# Callisto_MSO_Teknic_v1p00.net
KiCad netlist of a schematic drawn in EAGLE
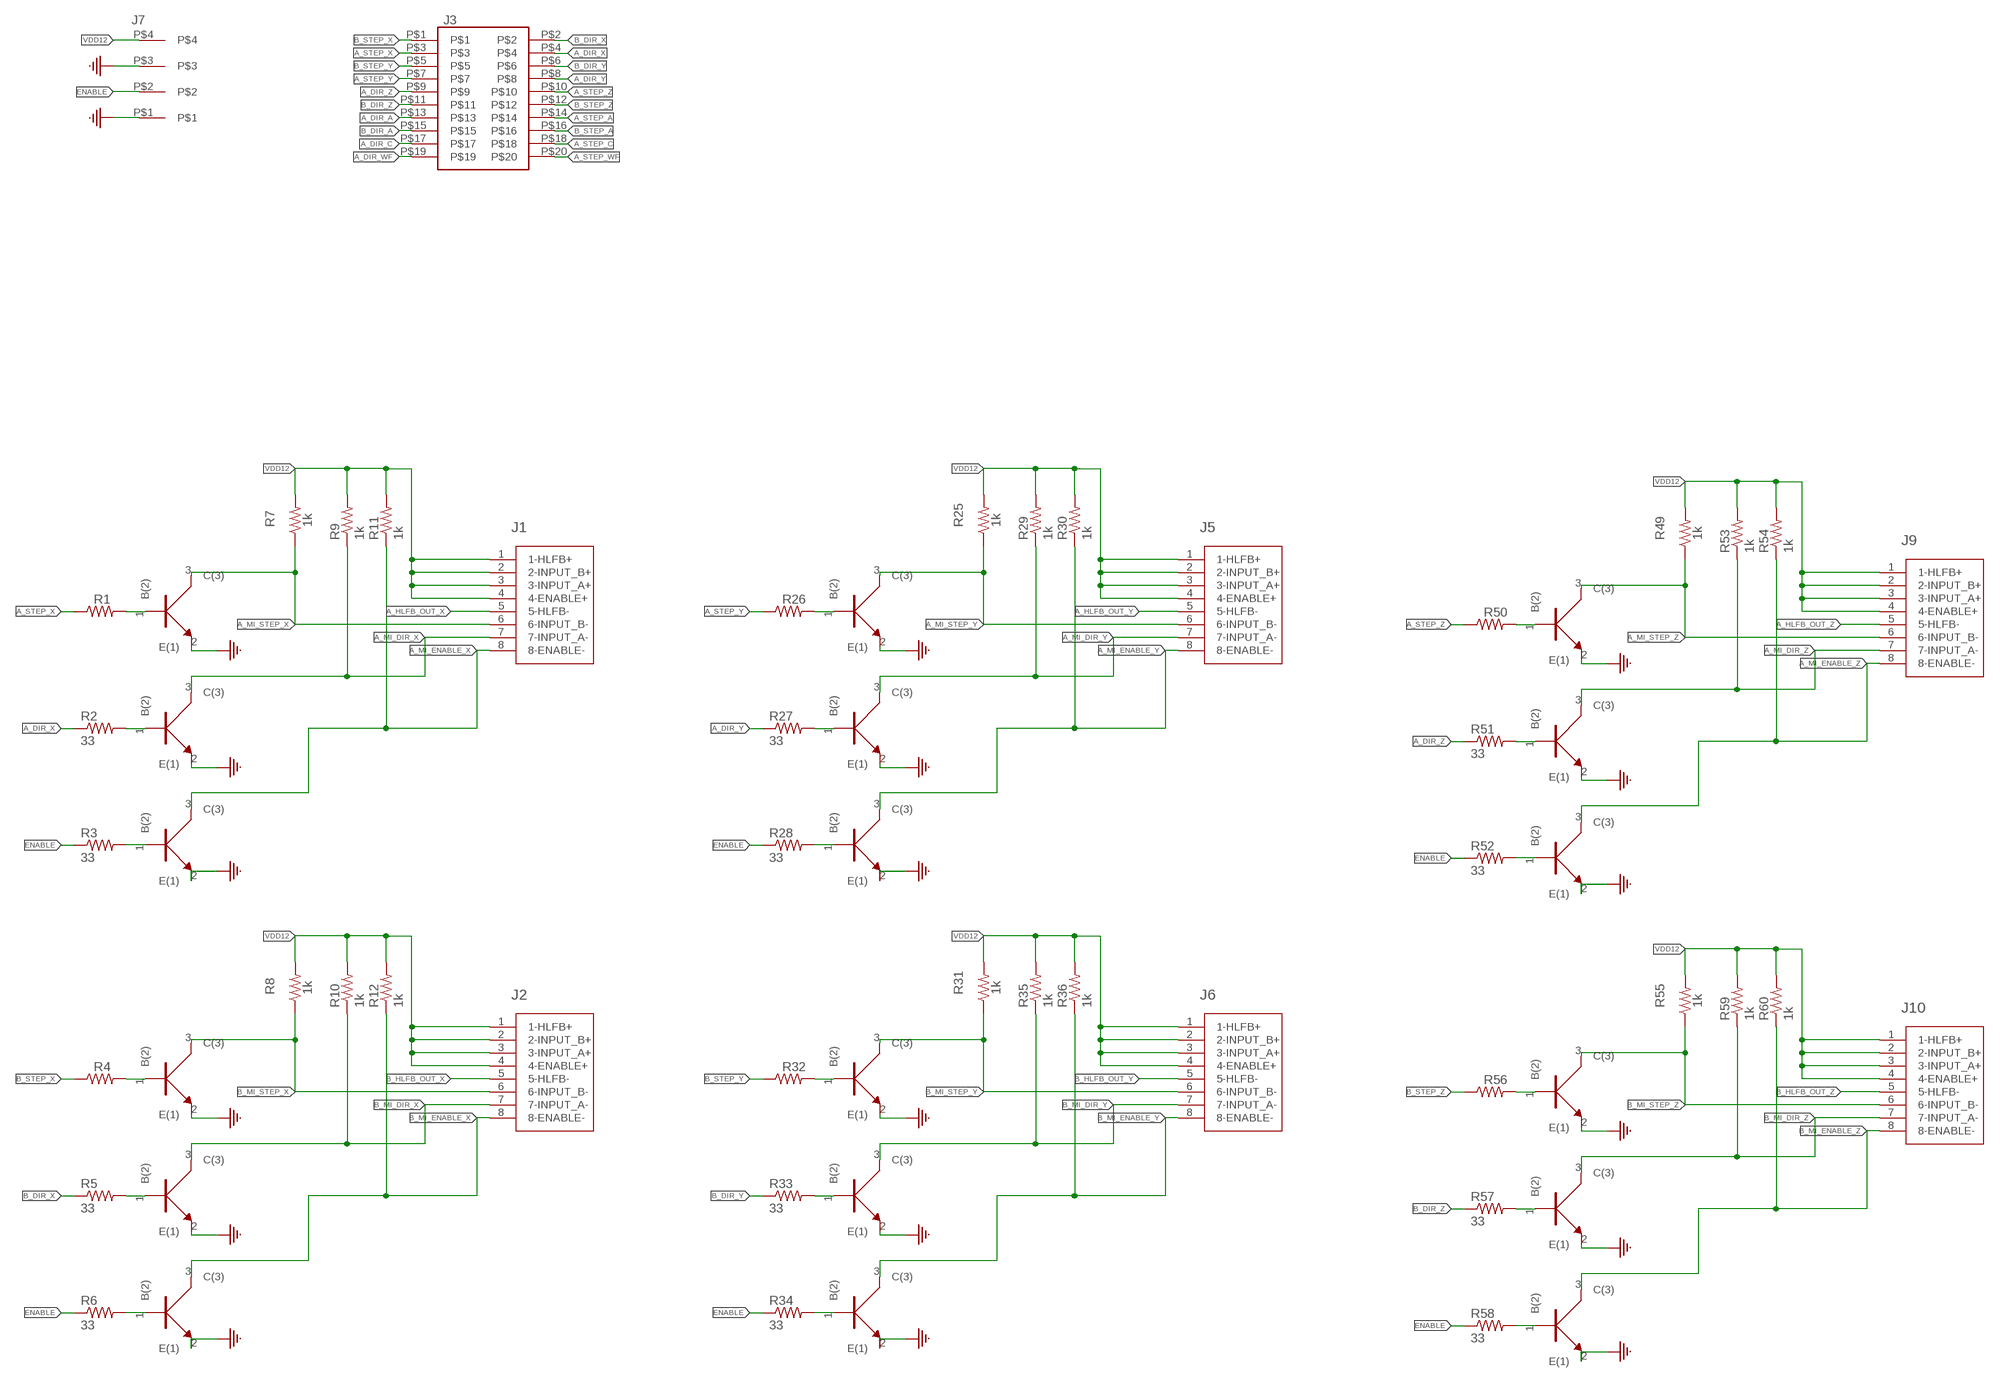
[diagram p0: schematic, sheet 1, part 1 of 2]
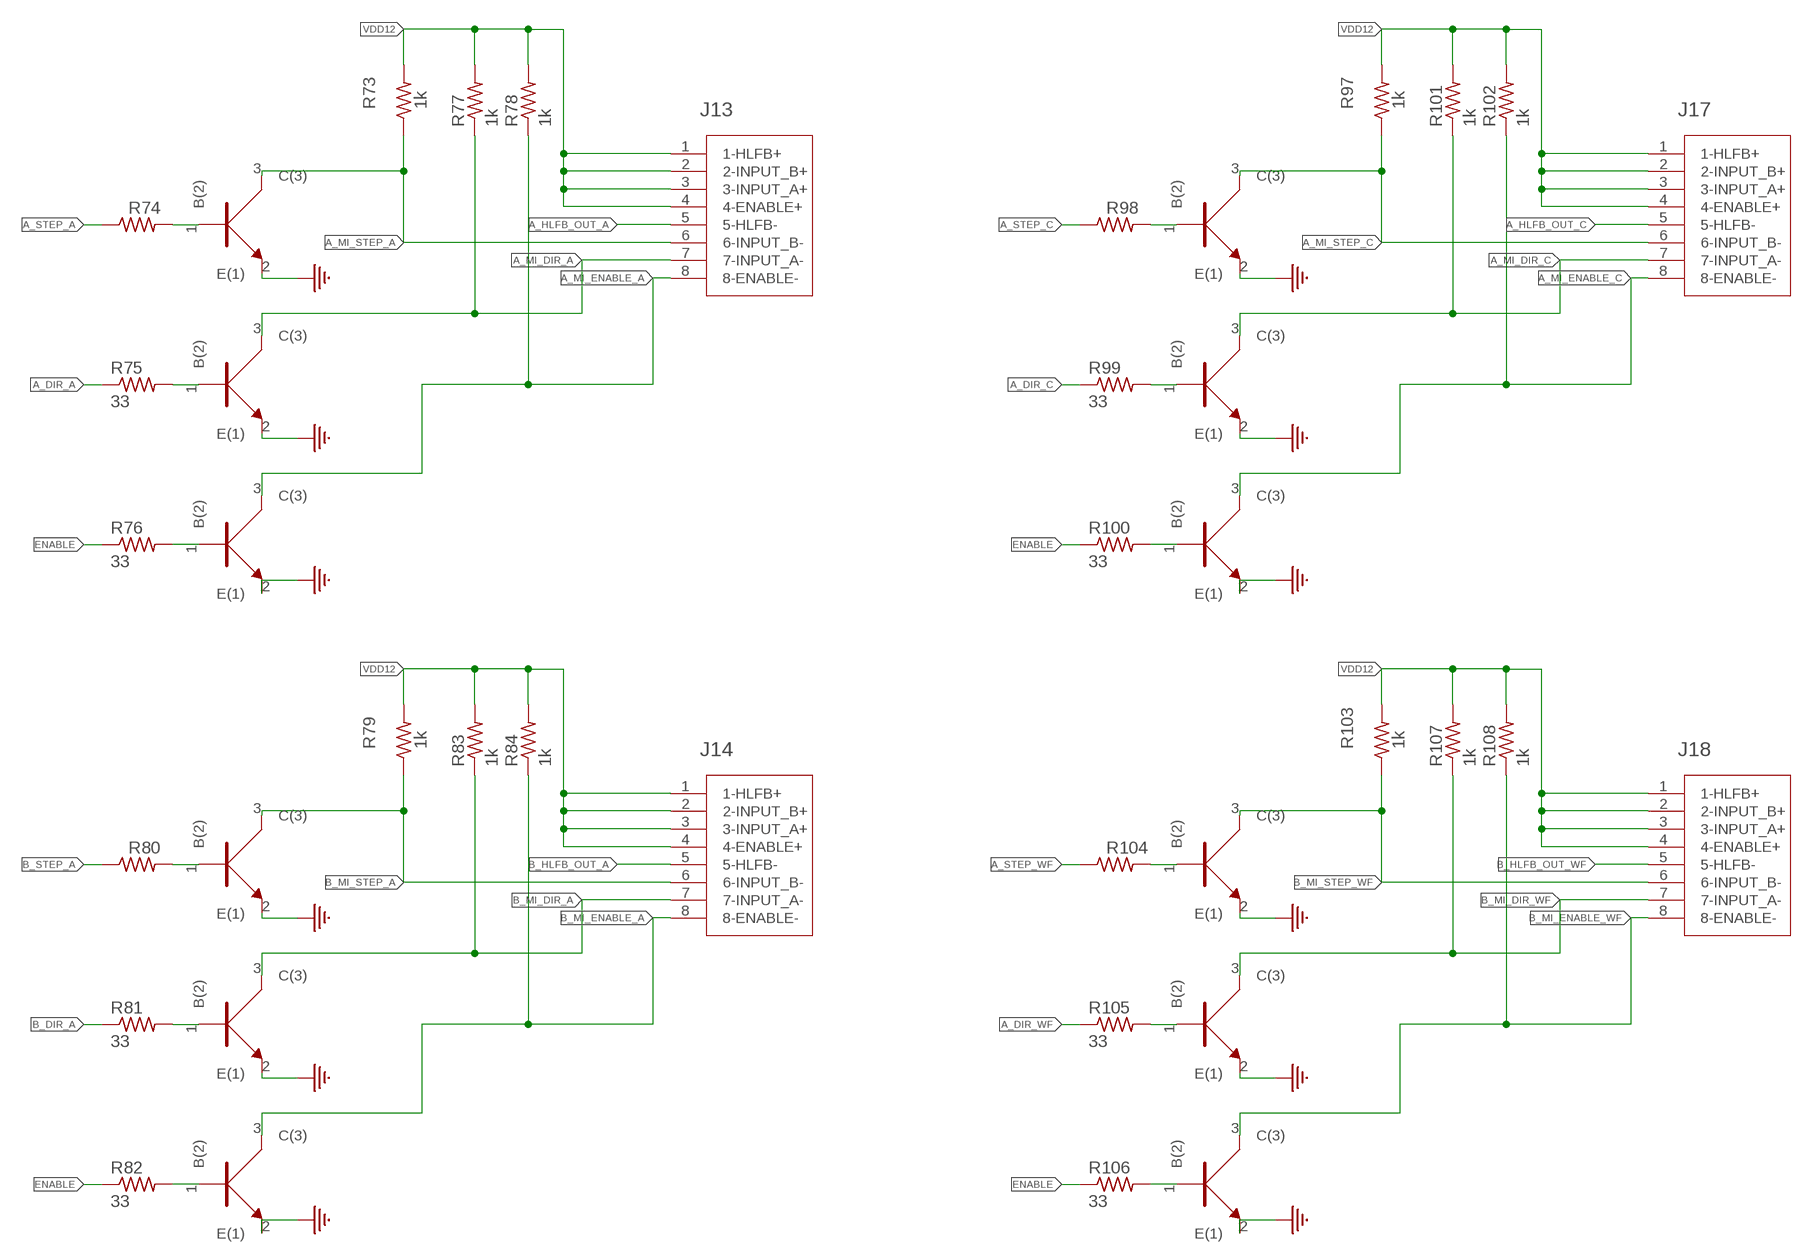
[diagram p1: schematic, sheet 1, part 2 of 2]

(export (version "E")
  (design (tool "Eeschema 10.0.6"))
  (components
    (comp (ref "J1")
      (value "TEKNIC_8PIN_MOTOR")
      (footprint "eagle-import:CON_39281083")
      (fields
        (field (name "MANUFACTURER_PART_NUMBER") "39281083")
        (field (name "COPYRIGHT") "Copyright (C) 2022 Ultra Librarian. All rights reserved.")
      )
      (libsource (lib "eagle-import") (part "TEKNIC_8PIN_MOTOR"))
    )
    (comp (ref "J2")
      (value "TEKNIC_8PIN_MOTOR")
      (footprint "eagle-import:CON_39281083")
      (fields
        (field (name "MANUFACTURER_PART_NUMBER") "39281083")
        (field (name "COPYRIGHT") "Copyright (C) 2022 Ultra Librarian. All rights reserved.")
      )
      (libsource (lib "eagle-import") (part "TEKNIC_8PIN_MOTOR"))
    )
    (comp (ref "J3")
      (value "2_X_10_HEADER_GENERIC2_X_10_.1_IN_RA")
      (footprint "eagle-import:2_X_10_.1_INCH")
      (fields (field (name "PARTNO") "PH2RA-20-UA"))
      (libsource (lib "eagle-import") (part "2_X_10_HEADER_GENERIC2_X_10_.1_IN_RA"))
    )
    (comp (ref "J5")
      (value "TEKNIC_8PIN_MOTOR")
      (footprint "eagle-import:CON_39281083")
      (fields
        (field (name "MANUFACTURER_PART_NUMBER") "39281083")
        (field (name "COPYRIGHT") "Copyright (C) 2022 Ultra Librarian. All rights reserved.")
      )
      (libsource (lib "eagle-import") (part "TEKNIC_8PIN_MOTOR"))
    )
    (comp (ref "J6")
      (value "TEKNIC_8PIN_MOTOR")
      (footprint "eagle-import:CON_39281083")
      (fields
        (field (name "MANUFACTURER_PART_NUMBER") "39281083")
        (field (name "COPYRIGHT") "Copyright (C) 2022 Ultra Librarian. All rights reserved.")
      )
      (libsource (lib "eagle-import") (part "TEKNIC_8PIN_MOTOR"))
    )
    (comp (ref "J7")
      (value "4-pos")
      (footprint "eagle-import:1X4_3.81MM_PITCH")
      (fields (field (name "PARTNO") "691322310004"))
      (libsource (lib "eagle-import") (part "3.81MM_1_X_4_RT_ANGLE_PLUG_HEADER"))
    )
    (comp (ref "J9")
      (value "TEKNIC_8PIN_MOTOR")
      (footprint "eagle-import:CON_39281083")
      (fields
        (field (name "MANUFACTURER_PART_NUMBER") "39281083")
        (field (name "COPYRIGHT") "Copyright (C) 2022 Ultra Librarian. All rights reserved.")
      )
      (libsource (lib "eagle-import") (part "TEKNIC_8PIN_MOTOR"))
    )
    (comp (ref "J10")
      (value "TEKNIC_8PIN_MOTOR")
      (footprint "eagle-import:CON_39281083")
      (fields
        (field (name "MANUFACTURER_PART_NUMBER") "39281083")
        (field (name "COPYRIGHT") "Copyright (C) 2022 Ultra Librarian. All rights reserved.")
      )
      (libsource (lib "eagle-import") (part "TEKNIC_8PIN_MOTOR"))
    )
    (comp (ref "J13")
      (value "TEKNIC_8PIN_MOTOR")
      (footprint "eagle-import:CON_39281083")
      (fields
        (field (name "MANUFACTURER_PART_NUMBER") "39281083")
        (field (name "COPYRIGHT") "Copyright (C) 2022 Ultra Librarian. All rights reserved.")
      )
      (libsource (lib "eagle-import") (part "TEKNIC_8PIN_MOTOR"))
    )
    (comp (ref "J14")
      (value "TEKNIC_8PIN_MOTOR")
      (footprint "eagle-import:CON_39281083")
      (fields
        (field (name "MANUFACTURER_PART_NUMBER") "39281083")
        (field (name "COPYRIGHT") "Copyright (C) 2022 Ultra Librarian. All rights reserved.")
      )
      (libsource (lib "eagle-import") (part "TEKNIC_8PIN_MOTOR"))
    )
    (comp (ref "J17")
      (value "TEKNIC_8PIN_MOTOR")
      (footprint "eagle-import:CON_39281083")
      (fields
        (field (name "MANUFACTURER_PART_NUMBER") "39281083")
        (field (name "COPYRIGHT") "Copyright (C) 2022 Ultra Librarian. All rights reserved.")
      )
      (libsource (lib "eagle-import") (part "TEKNIC_8PIN_MOTOR"))
    )
    (comp (ref "J18")
      (value "TEKNIC_8PIN_MOTOR")
      (footprint "eagle-import:CON_39281083")
      (fields
        (field (name "MANUFACTURER_PART_NUMBER") "39281083")
        (field (name "COPYRIGHT") "Copyright (C) 2022 Ultra Librarian. All rights reserved.")
      )
      (libsource (lib "eagle-import") (part "TEKNIC_8PIN_MOTOR"))
    )
    (comp (ref "R1")
      (value "33")
      (footprint "eagle-import:0805")
      (libsource (lib "eagle-import") (part "R_0805"))
    )
    (comp (ref "R2")
      (value "33")
      (footprint "eagle-import:0805")
      (libsource (lib "eagle-import") (part "R_0805"))
    )
    (comp (ref "R3")
      (value "33")
      (footprint "eagle-import:0805")
      (libsource (lib "eagle-import") (part "R_0805"))
    )
    (comp (ref "R4")
      (value "33")
      (footprint "eagle-import:0805")
      (libsource (lib "eagle-import") (part "R_0805"))
    )
    (comp (ref "R5")
      (value "33")
      (footprint "eagle-import:0805")
      (libsource (lib "eagle-import") (part "R_0805"))
    )
    (comp (ref "R6")
      (value "33")
      (footprint "eagle-import:0805")
      (libsource (lib "eagle-import") (part "R_0805"))
    )
    (comp (ref "R7")
      (value "1k")
      (footprint "eagle-import:0805")
      (libsource (lib "eagle-import") (part "R_0805"))
    )
    (comp (ref "R8")
      (value "1k")
      (footprint "eagle-import:0805")
      (libsource (lib "eagle-import") (part "R_0805"))
    )
    (comp (ref "R9")
      (value "1k")
      (footprint "eagle-import:0805")
      (libsource (lib "eagle-import") (part "R_0805"))
    )
    (comp (ref "R10")
      (value "1k")
      (footprint "eagle-import:0805")
      (libsource (lib "eagle-import") (part "R_0805"))
    )
    (comp (ref "R11")
      (value "1k")
      (footprint "eagle-import:0805")
      (libsource (lib "eagle-import") (part "R_0805"))
    )
    (comp (ref "R12")
      (value "1k")
      (footprint "eagle-import:0805")
      (libsource (lib "eagle-import") (part "R_0805"))
    )
    (comp (ref "R25")
      (value "1k")
      (footprint "eagle-import:0805")
      (libsource (lib "eagle-import") (part "R_0805"))
    )
    (comp (ref "R26")
      (value "33")
      (footprint "eagle-import:0805")
      (libsource (lib "eagle-import") (part "R_0805"))
    )
    (comp (ref "R27")
      (value "33")
      (footprint "eagle-import:0805")
      (libsource (lib "eagle-import") (part "R_0805"))
    )
    (comp (ref "R28")
      (value "33")
      (footprint "eagle-import:0805")
      (libsource (lib "eagle-import") (part "R_0805"))
    )
    (comp (ref "R29")
      (value "1k")
      (footprint "eagle-import:0805")
      (libsource (lib "eagle-import") (part "R_0805"))
    )
    (comp (ref "R30")
      (value "1k")
      (footprint "eagle-import:0805")
      (libsource (lib "eagle-import") (part "R_0805"))
    )
    (comp (ref "R31")
      (value "1k")
      (footprint "eagle-import:0805")
      (libsource (lib "eagle-import") (part "R_0805"))
    )
    (comp (ref "R32")
      (value "33")
      (footprint "eagle-import:0805")
      (libsource (lib "eagle-import") (part "R_0805"))
    )
    (comp (ref "R33")
      (value "33")
      (footprint "eagle-import:0805")
      (libsource (lib "eagle-import") (part "R_0805"))
    )
    (comp (ref "R34")
      (value "33")
      (footprint "eagle-import:0805")
      (libsource (lib "eagle-import") (part "R_0805"))
    )
    (comp (ref "R35")
      (value "1k")
      (footprint "eagle-import:0805")
      (libsource (lib "eagle-import") (part "R_0805"))
    )
    (comp (ref "R36")
      (value "1k")
      (footprint "eagle-import:0805")
      (libsource (lib "eagle-import") (part "R_0805"))
    )
    (comp (ref "R49")
      (value "1k")
      (footprint "eagle-import:0805")
      (libsource (lib "eagle-import") (part "R_0805"))
    )
    (comp (ref "R50")
      (value "33")
      (footprint "eagle-import:0805")
      (libsource (lib "eagle-import") (part "R_0805"))
    )
    (comp (ref "R51")
      (value "33")
      (footprint "eagle-import:0805")
      (libsource (lib "eagle-import") (part "R_0805"))
    )
    (comp (ref "R52")
      (value "33")
      (footprint "eagle-import:0805")
      (libsource (lib "eagle-import") (part "R_0805"))
    )
    (comp (ref "R53")
      (value "1k")
      (footprint "eagle-import:0805")
      (libsource (lib "eagle-import") (part "R_0805"))
    )
    (comp (ref "R54")
      (value "1k")
      (footprint "eagle-import:0805")
      (libsource (lib "eagle-import") (part "R_0805"))
    )
    (comp (ref "R55")
      (value "1k")
      (footprint "eagle-import:0805")
      (libsource (lib "eagle-import") (part "R_0805"))
    )
    (comp (ref "R56")
      (value "33")
      (footprint "eagle-import:0805")
      (libsource (lib "eagle-import") (part "R_0805"))
    )
    (comp (ref "R57")
      (value "33")
      (footprint "eagle-import:0805")
      (libsource (lib "eagle-import") (part "R_0805"))
    )
    (comp (ref "R58")
      (value "33")
      (footprint "eagle-import:0805")
      (libsource (lib "eagle-import") (part "R_0805"))
    )
    (comp (ref "R59")
      (value "1k")
      (footprint "eagle-import:0805")
      (libsource (lib "eagle-import") (part "R_0805"))
    )
    (comp (ref "R60")
      (value "1k")
      (footprint "eagle-import:0805")
      (libsource (lib "eagle-import") (part "R_0805"))
    )
    (comp (ref "R73")
      (value "1k")
      (footprint "eagle-import:0805")
      (libsource (lib "eagle-import") (part "R_0805"))
    )
    (comp (ref "R74")
      (value "33")
      (footprint "eagle-import:0805")
      (libsource (lib "eagle-import") (part "R_0805"))
    )
    (comp (ref "R75")
      (value "33")
      (footprint "eagle-import:0805")
      (libsource (lib "eagle-import") (part "R_0805"))
    )
    (comp (ref "R76")
      (value "33")
      (footprint "eagle-import:0805")
      (libsource (lib "eagle-import") (part "R_0805"))
    )
    (comp (ref "R77")
      (value "1k")
      (footprint "eagle-import:0805")
      (libsource (lib "eagle-import") (part "R_0805"))
    )
    (comp (ref "R78")
      (value "1k")
      (footprint "eagle-import:0805")
      (libsource (lib "eagle-import") (part "R_0805"))
    )
    (comp (ref "R79")
      (value "1k")
      (footprint "eagle-import:0805")
      (libsource (lib "eagle-import") (part "R_0805"))
    )
    (comp (ref "R80")
      (value "33")
      (footprint "eagle-import:0805")
      (libsource (lib "eagle-import") (part "R_0805"))
    )
    (comp (ref "R81")
      (value "33")
      (footprint "eagle-import:0805")
      (libsource (lib "eagle-import") (part "R_0805"))
    )
    (comp (ref "R82")
      (value "33")
      (footprint "eagle-import:0805")
      (libsource (lib "eagle-import") (part "R_0805"))
    )
    (comp (ref "R83")
      (value "1k")
      (footprint "eagle-import:0805")
      (libsource (lib "eagle-import") (part "R_0805"))
    )
    (comp (ref "R84")
      (value "1k")
      (footprint "eagle-import:0805")
      (libsource (lib "eagle-import") (part "R_0805"))
    )
    (comp (ref "R97")
      (value "1k")
      (footprint "eagle-import:0805")
      (libsource (lib "eagle-import") (part "R_0805"))
    )
    (comp (ref "R98")
      (value "33")
      (footprint "eagle-import:0805")
      (libsource (lib "eagle-import") (part "R_0805"))
    )
    (comp (ref "R99")
      (value "33")
      (footprint "eagle-import:0805")
      (libsource (lib "eagle-import") (part "R_0805"))
    )
    (comp (ref "R100")
      (value "33")
      (footprint "eagle-import:0805")
      (libsource (lib "eagle-import") (part "R_0805"))
    )
    (comp (ref "R101")
      (value "1k")
      (footprint "eagle-import:0805")
      (libsource (lib "eagle-import") (part "R_0805"))
    )
    (comp (ref "R102")
      (value "1k")
      (footprint "eagle-import:0805")
      (libsource (lib "eagle-import") (part "R_0805"))
    )
    (comp (ref "R103")
      (value "1k")
      (footprint "eagle-import:0805")
      (libsource (lib "eagle-import") (part "R_0805"))
    )
    (comp (ref "R104")
      (value "33")
      (footprint "eagle-import:0805")
      (libsource (lib "eagle-import") (part "R_0805"))
    )
    (comp (ref "R105")
      (value "33")
      (footprint "eagle-import:0805")
      (libsource (lib "eagle-import") (part "R_0805"))
    )
    (comp (ref "R106")
      (value "33")
      (footprint "eagle-import:0805")
      (libsource (lib "eagle-import") (part "R_0805"))
    )
    (comp (ref "R107")
      (value "1k")
      (footprint "eagle-import:0805")
      (libsource (lib "eagle-import") (part "R_0805"))
    )
    (comp (ref "R108")
      (value "1k")
      (footprint "eagle-import:0805")
      (libsource (lib "eagle-import") (part "R_0805"))
    )
    (comp (ref "U1")
      (value "NPN")
      (footprint "eagle-import:SOT323")
      (fields (field (name "PARTNO") "BC846BW_NPN"))
      (libsource (lib "eagle-import") (part "BC846BW"))
    )
    (comp (ref "U2")
      (value "NPN")
      (footprint "eagle-import:SOT323")
      (fields (field (name "PARTNO") "BC846BW_NPN"))
      (libsource (lib "eagle-import") (part "BC846BW"))
    )
    (comp (ref "U3")
      (value "NPN")
      (footprint "eagle-import:SOT323")
      (fields (field (name "PARTNO") "BC846BW_NPN"))
      (libsource (lib "eagle-import") (part "BC846BW"))
    )
    (comp (ref "U4")
      (value "NPN")
      (footprint "eagle-import:SOT323")
      (fields (field (name "PARTNO") "BC846BW_NPN"))
      (libsource (lib "eagle-import") (part "BC846BW"))
    )
    (comp (ref "U5")
      (value "NPN")
      (footprint "eagle-import:SOT323")
      (fields (field (name "PARTNO") "BC846BW_NPN"))
      (libsource (lib "eagle-import") (part "BC846BW"))
    )
    (comp (ref "U6")
      (value "NPN")
      (footprint "eagle-import:SOT323")
      (fields (field (name "PARTNO") "BC846BW_NPN"))
      (libsource (lib "eagle-import") (part "BC846BW"))
    )
    (comp (ref "U13")
      (value "NPN")
      (footprint "eagle-import:SOT323")
      (fields (field (name "PARTNO") "BC846BW_NPN"))
      (libsource (lib "eagle-import") (part "BC846BW"))
    )
    (comp (ref "U14")
      (value "NPN")
      (footprint "eagle-import:SOT323")
      (fields (field (name "PARTNO") "BC846BW_NPN"))
      (libsource (lib "eagle-import") (part "BC846BW"))
    )
    (comp (ref "U15")
      (value "NPN")
      (footprint "eagle-import:SOT323")
      (fields (field (name "PARTNO") "BC846BW_NPN"))
      (libsource (lib "eagle-import") (part "BC846BW"))
    )
    (comp (ref "U16")
      (value "NPN")
      (footprint "eagle-import:SOT323")
      (fields (field (name "PARTNO") "BC846BW_NPN"))
      (libsource (lib "eagle-import") (part "BC846BW"))
    )
    (comp (ref "U17")
      (value "NPN")
      (footprint "eagle-import:SOT323")
      (fields (field (name "PARTNO") "BC846BW_NPN"))
      (libsource (lib "eagle-import") (part "BC846BW"))
    )
    (comp (ref "U18")
      (value "NPN")
      (footprint "eagle-import:SOT323")
      (fields (field (name "PARTNO") "BC846BW_NPN"))
      (libsource (lib "eagle-import") (part "BC846BW"))
    )
    (comp (ref "U25")
      (value "NPN")
      (footprint "eagle-import:SOT323")
      (fields (field (name "PARTNO") "BC846BW_NPN"))
      (libsource (lib "eagle-import") (part "BC846BW"))
    )
    (comp (ref "U26")
      (value "NPN")
      (footprint "eagle-import:SOT323")
      (fields (field (name "PARTNO") "BC846BW_NPN"))
      (libsource (lib "eagle-import") (part "BC846BW"))
    )
    (comp (ref "U27")
      (value "NPN")
      (footprint "eagle-import:SOT323")
      (fields (field (name "PARTNO") "BC846BW_NPN"))
      (libsource (lib "eagle-import") (part "BC846BW"))
    )
    (comp (ref "U28")
      (value "NPN")
      (footprint "eagle-import:SOT323")
      (fields (field (name "PARTNO") "BC846BW_NPN"))
      (libsource (lib "eagle-import") (part "BC846BW"))
    )
    (comp (ref "U29")
      (value "NPN")
      (footprint "eagle-import:SOT323")
      (fields (field (name "PARTNO") "BC846BW_NPN"))
      (libsource (lib "eagle-import") (part "BC846BW"))
    )
    (comp (ref "U30")
      (value "NPN")
      (footprint "eagle-import:SOT323")
      (fields (field (name "PARTNO") "BC846BW_NPN"))
      (libsource (lib "eagle-import") (part "BC846BW"))
    )
    (comp (ref "U37")
      (value "NPN")
      (footprint "eagle-import:SOT323")
      (fields (field (name "PARTNO") "BC846BW_NPN"))
      (libsource (lib "eagle-import") (part "BC846BW"))
    )
    (comp (ref "U38")
      (value "NPN")
      (footprint "eagle-import:SOT323")
      (fields (field (name "PARTNO") "BC846BW_NPN"))
      (libsource (lib "eagle-import") (part "BC846BW"))
    )
    (comp (ref "U39")
      (value "NPN")
      (footprint "eagle-import:SOT323")
      (fields (field (name "PARTNO") "BC846BW_NPN"))
      (libsource (lib "eagle-import") (part "BC846BW"))
    )
    (comp (ref "U40")
      (value "NPN")
      (footprint "eagle-import:SOT323")
      (fields (field (name "PARTNO") "BC846BW_NPN"))
      (libsource (lib "eagle-import") (part "BC846BW"))
    )
    (comp (ref "U41")
      (value "NPN")
      (footprint "eagle-import:SOT323")
      (fields (field (name "PARTNO") "BC846BW_NPN"))
      (libsource (lib "eagle-import") (part "BC846BW"))
    )
    (comp (ref "U42")
      (value "NPN")
      (footprint "eagle-import:SOT323")
      (fields (field (name "PARTNO") "BC846BW_NPN"))
      (libsource (lib "eagle-import") (part "BC846BW"))
    )
    (comp (ref "U49")
      (value "NPN")
      (footprint "eagle-import:SOT323")
      (fields (field (name "PARTNO") "BC846BW_NPN"))
      (libsource (lib "eagle-import") (part "BC846BW"))
    )
    (comp (ref "U50")
      (value "NPN")
      (footprint "eagle-import:SOT323")
      (fields (field (name "PARTNO") "BC846BW_NPN"))
      (libsource (lib "eagle-import") (part "BC846BW"))
    )
    (comp (ref "U51")
      (value "NPN")
      (footprint "eagle-import:SOT323")
      (fields (field (name "PARTNO") "BC846BW_NPN"))
      (libsource (lib "eagle-import") (part "BC846BW"))
    )
    (comp (ref "U52")
      (value "NPN")
      (footprint "eagle-import:SOT323")
      (fields (field (name "PARTNO") "BC846BW_NPN"))
      (libsource (lib "eagle-import") (part "BC846BW"))
    )
    (comp (ref "U53")
      (value "NPN")
      (footprint "eagle-import:SOT323")
      (fields (field (name "PARTNO") "BC846BW_NPN"))
      (libsource (lib "eagle-import") (part "BC846BW"))
    )
    (comp (ref "U54")
      (value "NPN")
      (footprint "eagle-import:SOT323")
      (fields (field (name "PARTNO") "BC846BW_NPN"))
      (libsource (lib "eagle-import") (part "BC846BW"))
    )
  )
  (nets
    (net (code "1") (name "A_DIR_A") (class "Default")
      (node (ref "J3") (pin "P$13") (pinfunction "P$13_P$13") (pintype "bidirectional"))
      (node (ref "R75") (pin "1") (pinfunction "1_1") (pintype "passive"))
    )
    (net (code "2") (name "A_DIR_C") (class "Default")
      (node (ref "J3") (pin "P$17") (pinfunction "P$17_P$17") (pintype "bidirectional"))
      (node (ref "R99") (pin "1") (pinfunction "1_1") (pintype "passive"))
    )
    (net (code "3") (name "A_DIR_WF") (class "Default")
      (node (ref "J3") (pin "P$19") (pinfunction "P$19_P$19") (pintype "bidirectional"))
      (node (ref "R105") (pin "1") (pinfunction "1_1") (pintype "passive"))
    )
    (net (code "4") (name "A_DIR_X") (class "Default")
      (node (ref "J3") (pin "P$4") (pinfunction "P$4_P$4") (pintype "bidirectional"))
      (node (ref "R2") (pin "1") (pinfunction "1_1") (pintype "passive"))
    )
    (net (code "5") (name "A_DIR_Y") (class "Default")
      (node (ref "J3") (pin "P$8") (pinfunction "P$8_P$8") (pintype "bidirectional"))
      (node (ref "R27") (pin "1") (pinfunction "1_1") (pintype "passive"))
    )
    (net (code "6") (name "A_DIR_Z") (class "Default")
      (node (ref "J3") (pin "P$9") (pinfunction "P$9_P$9") (pintype "bidirectional"))
      (node (ref "R51") (pin "1") (pinfunction "1_1") (pintype "passive"))
    )
    (net (code "7") (name "A_HLFB_OUT_A") (class "Default")
      (node (ref "J13") (pin "5") (pinfunction "5-HLFB-_5") (pintype "passive"))
    )
    (net (code "8") (name "A_HLFB_OUT_C") (class "Default")
      (node (ref "J17") (pin "5") (pinfunction "5-HLFB-_5") (pintype "passive"))
    )
    (net (code "9") (name "A_HLFB_OUT_X") (class "Default")
      (node (ref "J1") (pin "5") (pinfunction "5-HLFB-_5") (pintype "passive"))
    )
    (net (code "10") (name "A_HLFB_OUT_Y") (class "Default")
      (node (ref "J5") (pin "5") (pinfunction "5-HLFB-_5") (pintype "passive"))
    )
    (net (code "11") (name "A_HLFB_OUT_Z") (class "Default")
      (node (ref "J9") (pin "5") (pinfunction "5-HLFB-_5") (pintype "passive"))
    )
    (net (code "12") (name "A_MI_DIR_A") (class "Default")
      (node (ref "J13") (pin "7") (pinfunction "7-INPUT_A-_7") (pintype "passive"))
      (node (ref "R77") (pin "1") (pinfunction "1_1") (pintype "passive"))
      (node (ref "U38") (pin "3") (pinfunction "C(3)_3") (pintype "input"))
    )
    (net (code "13") (name "A_MI_DIR_C") (class "Default")
      (node (ref "J17") (pin "7") (pinfunction "7-INPUT_A-_7") (pintype "passive"))
      (node (ref "R101") (pin "1") (pinfunction "1_1") (pintype "passive"))
      (node (ref "U50") (pin "3") (pinfunction "C(3)_3") (pintype "input"))
    )
    (net (code "14") (name "A_MI_DIR_X") (class "Default")
      (node (ref "J1") (pin "7") (pinfunction "7-INPUT_A-_7") (pintype "passive"))
      (node (ref "R9") (pin "1") (pinfunction "1_1") (pintype "passive"))
      (node (ref "U2") (pin "3") (pinfunction "C(3)_3") (pintype "input"))
    )
    (net (code "15") (name "A_MI_DIR_Y") (class "Default")
      (node (ref "J5") (pin "7") (pinfunction "7-INPUT_A-_7") (pintype "passive"))
      (node (ref "R29") (pin "1") (pinfunction "1_1") (pintype "passive"))
      (node (ref "U14") (pin "3") (pinfunction "C(3)_3") (pintype "input"))
    )
    (net (code "16") (name "A_MI_DIR_Z") (class "Default")
      (node (ref "J9") (pin "7") (pinfunction "7-INPUT_A-_7") (pintype "passive"))
      (node (ref "R53") (pin "1") (pinfunction "1_1") (pintype "passive"))
      (node (ref "U26") (pin "3") (pinfunction "C(3)_3") (pintype "input"))
    )
    (net (code "17") (name "A_MI_ENABLE_A") (class "Default")
      (node (ref "J13") (pin "8") (pinfunction "8-ENABLE-_8") (pintype "passive"))
      (node (ref "R78") (pin "1") (pinfunction "1_1") (pintype "passive"))
      (node (ref "U39") (pin "3") (pinfunction "C(3)_3") (pintype "input"))
    )
    (net (code "18") (name "A_MI_ENABLE_C") (class "Default")
      (node (ref "J17") (pin "8") (pinfunction "8-ENABLE-_8") (pintype "passive"))
      (node (ref "R102") (pin "1") (pinfunction "1_1") (pintype "passive"))
      (node (ref "U51") (pin "3") (pinfunction "C(3)_3") (pintype "input"))
    )
    (net (code "19") (name "A_MI_ENABLE_X") (class "Default")
      (node (ref "J1") (pin "8") (pinfunction "8-ENABLE-_8") (pintype "passive"))
      (node (ref "R11") (pin "1") (pinfunction "1_1") (pintype "passive"))
      (node (ref "U3") (pin "3") (pinfunction "C(3)_3") (pintype "input"))
    )
    (net (code "20") (name "A_MI_ENABLE_Y") (class "Default")
      (node (ref "J5") (pin "8") (pinfunction "8-ENABLE-_8") (pintype "passive"))
      (node (ref "R30") (pin "1") (pinfunction "1_1") (pintype "passive"))
      (node (ref "U15") (pin "3") (pinfunction "C(3)_3") (pintype "input"))
    )
    (net (code "21") (name "A_MI_ENABLE_Z") (class "Default")
      (node (ref "J9") (pin "8") (pinfunction "8-ENABLE-_8") (pintype "passive"))
      (node (ref "R54") (pin "1") (pinfunction "1_1") (pintype "passive"))
      (node (ref "U27") (pin "3") (pinfunction "C(3)_3") (pintype "input"))
    )
    (net (code "22") (name "A_MI_STEP_A") (class "Default")
      (node (ref "J13") (pin "6") (pinfunction "6-INPUT_B-_6") (pintype "passive"))
      (node (ref "R73") (pin "1") (pinfunction "1_1") (pintype "passive"))
      (node (ref "U37") (pin "3") (pinfunction "C(3)_3") (pintype "input"))
    )
    (net (code "23") (name "A_MI_STEP_C") (class "Default")
      (node (ref "J17") (pin "6") (pinfunction "6-INPUT_B-_6") (pintype "passive"))
      (node (ref "R97") (pin "1") (pinfunction "1_1") (pintype "passive"))
      (node (ref "U49") (pin "3") (pinfunction "C(3)_3") (pintype "input"))
    )
    (net (code "24") (name "A_MI_STEP_X") (class "Default")
      (node (ref "J1") (pin "6") (pinfunction "6-INPUT_B-_6") (pintype "passive"))
      (node (ref "R7") (pin "1") (pinfunction "1_1") (pintype "passive"))
      (node (ref "U1") (pin "3") (pinfunction "C(3)_3") (pintype "input"))
    )
    (net (code "25") (name "A_MI_STEP_Y") (class "Default")
      (node (ref "J5") (pin "6") (pinfunction "6-INPUT_B-_6") (pintype "passive"))
      (node (ref "R25") (pin "1") (pinfunction "1_1") (pintype "passive"))
      (node (ref "U13") (pin "3") (pinfunction "C(3)_3") (pintype "input"))
    )
    (net (code "26") (name "A_MI_STEP_Z") (class "Default")
      (node (ref "J9") (pin "6") (pinfunction "6-INPUT_B-_6") (pintype "passive"))
      (node (ref "R49") (pin "1") (pinfunction "1_1") (pintype "passive"))
      (node (ref "U25") (pin "3") (pinfunction "C(3)_3") (pintype "input"))
    )
    (net (code "27") (name "A_STEP_A") (class "Default")
      (node (ref "J3") (pin "P$14") (pinfunction "P$14_P$14") (pintype "bidirectional"))
      (node (ref "R74") (pin "1") (pinfunction "1_1") (pintype "passive"))
    )
    (net (code "28") (name "A_STEP_C") (class "Default")
      (node (ref "J3") (pin "P$18") (pinfunction "P$18_P$18") (pintype "bidirectional"))
      (node (ref "R98") (pin "1") (pinfunction "1_1") (pintype "passive"))
    )
    (net (code "29") (name "A_STEP_WF") (class "Default")
      (node (ref "J3") (pin "P$20") (pinfunction "P$20_P$20") (pintype "bidirectional"))
      (node (ref "R104") (pin "1") (pinfunction "1_1") (pintype "passive"))
    )
    (net (code "30") (name "A_STEP_X") (class "Default")
      (node (ref "J3") (pin "P$3") (pinfunction "P$3_P$3") (pintype "bidirectional"))
      (node (ref "R1") (pin "1") (pinfunction "1_1") (pintype "passive"))
    )
    (net (code "31") (name "A_STEP_Y") (class "Default")
      (node (ref "J3") (pin "P$7") (pinfunction "P$7_P$7") (pintype "bidirectional"))
      (node (ref "R26") (pin "1") (pinfunction "1_1") (pintype "passive"))
    )
    (net (code "32") (name "A_STEP_Z") (class "Default")
      (node (ref "J3") (pin "P$10") (pinfunction "P$10_P$10") (pintype "bidirectional"))
      (node (ref "R50") (pin "1") (pinfunction "1_1") (pintype "passive"))
    )
    (net (code "33") (name "B_DIR_A") (class "Default")
      (node (ref "J3") (pin "P$15") (pinfunction "P$15_P$15") (pintype "bidirectional"))
      (node (ref "R81") (pin "1") (pinfunction "1_1") (pintype "passive"))
    )
    (net (code "34") (name "B_DIR_X") (class "Default")
      (node (ref "J3") (pin "P$2") (pinfunction "P$2_P$2") (pintype "bidirectional"))
      (node (ref "R5") (pin "1") (pinfunction "1_1") (pintype "passive"))
    )
    (net (code "35") (name "B_DIR_Y") (class "Default")
      (node (ref "J3") (pin "P$6") (pinfunction "P$6_P$6") (pintype "bidirectional"))
      (node (ref "R33") (pin "1") (pinfunction "1_1") (pintype "passive"))
    )
    (net (code "36") (name "B_DIR_Z") (class "Default")
      (node (ref "J3") (pin "P$11") (pinfunction "P$11_P$11") (pintype "bidirectional"))
      (node (ref "R57") (pin "1") (pinfunction "1_1") (pintype "passive"))
    )
    (net (code "37") (name "B_HLFB_OUT_A") (class "Default")
      (node (ref "J14") (pin "5") (pinfunction "5-HLFB-_5") (pintype "passive"))
    )
    (net (code "38") (name "B_HLFB_OUT_WF") (class "Default")
      (node (ref "J18") (pin "5") (pinfunction "5-HLFB-_5") (pintype "passive"))
    )
    (net (code "39") (name "B_HLFB_OUT_X") (class "Default")
      (node (ref "J2") (pin "5") (pinfunction "5-HLFB-_5") (pintype "passive"))
    )
    (net (code "40") (name "B_HLFB_OUT_Y") (class "Default")
      (node (ref "J6") (pin "5") (pinfunction "5-HLFB-_5") (pintype "passive"))
    )
    (net (code "41") (name "B_HLFB_OUT_Z") (class "Default")
      (node (ref "J10") (pin "5") (pinfunction "5-HLFB-_5") (pintype "passive"))
    )
    (net (code "42") (name "B_MI_DIR_A") (class "Default")
      (node (ref "J14") (pin "7") (pinfunction "7-INPUT_A-_7") (pintype "passive"))
      (node (ref "R83") (pin "1") (pinfunction "1_1") (pintype "passive"))
      (node (ref "U41") (pin "3") (pinfunction "C(3)_3") (pintype "input"))
    )
    (net (code "43") (name "B_MI_DIR_WF") (class "Default")
      (node (ref "J18") (pin "7") (pinfunction "7-INPUT_A-_7") (pintype "passive"))
      (node (ref "R107") (pin "1") (pinfunction "1_1") (pintype "passive"))
      (node (ref "U53") (pin "3") (pinfunction "C(3)_3") (pintype "input"))
    )
    (net (code "44") (name "B_MI_DIR_X") (class "Default")
      (node (ref "J2") (pin "7") (pinfunction "7-INPUT_A-_7") (pintype "passive"))
      (node (ref "R10") (pin "1") (pinfunction "1_1") (pintype "passive"))
      (node (ref "U5") (pin "3") (pinfunction "C(3)_3") (pintype "input"))
    )
    (net (code "45") (name "B_MI_DIR_Y") (class "Default")
      (node (ref "J6") (pin "7") (pinfunction "7-INPUT_A-_7") (pintype "passive"))
      (node (ref "R35") (pin "1") (pinfunction "1_1") (pintype "passive"))
      (node (ref "U17") (pin "3") (pinfunction "C(3)_3") (pintype "input"))
    )
    (net (code "46") (name "B_MI_DIR_Z") (class "Default")
      (node (ref "J10") (pin "7") (pinfunction "7-INPUT_A-_7") (pintype "passive"))
      (node (ref "R59") (pin "1") (pinfunction "1_1") (pintype "passive"))
      (node (ref "U29") (pin "3") (pinfunction "C(3)_3") (pintype "input"))
    )
    (net (code "47") (name "B_MI_ENABLE_A") (class "Default")
      (node (ref "J14") (pin "8") (pinfunction "8-ENABLE-_8") (pintype "passive"))
      (node (ref "R84") (pin "1") (pinfunction "1_1") (pintype "passive"))
      (node (ref "U42") (pin "3") (pinfunction "C(3)_3") (pintype "input"))
    )
    (net (code "48") (name "B_MI_ENABLE_WF") (class "Default")
      (node (ref "J18") (pin "8") (pinfunction "8-ENABLE-_8") (pintype "passive"))
      (node (ref "R108") (pin "1") (pinfunction "1_1") (pintype "passive"))
      (node (ref "U54") (pin "3") (pinfunction "C(3)_3") (pintype "input"))
    )
    (net (code "49") (name "B_MI_ENABLE_X") (class "Default")
      (node (ref "J2") (pin "8") (pinfunction "8-ENABLE-_8") (pintype "passive"))
      (node (ref "R12") (pin "1") (pinfunction "1_1") (pintype "passive"))
      (node (ref "U6") (pin "3") (pinfunction "C(3)_3") (pintype "input"))
    )
    (net (code "50") (name "B_MI_ENABLE_Y") (class "Default")
      (node (ref "J6") (pin "8") (pinfunction "8-ENABLE-_8") (pintype "passive"))
      (node (ref "R36") (pin "1") (pinfunction "1_1") (pintype "passive"))
      (node (ref "U18") (pin "3") (pinfunction "C(3)_3") (pintype "input"))
    )
    (net (code "51") (name "B_MI_ENABLE_Z") (class "Default")
      (node (ref "J10") (pin "8") (pinfunction "8-ENABLE-_8") (pintype "passive"))
      (node (ref "R60") (pin "1") (pinfunction "1_1") (pintype "passive"))
      (node (ref "U30") (pin "3") (pinfunction "C(3)_3") (pintype "input"))
    )
    (net (code "52") (name "B_MI_STEP_A") (class "Default")
      (node (ref "J14") (pin "6") (pinfunction "6-INPUT_B-_6") (pintype "passive"))
      (node (ref "R79") (pin "1") (pinfunction "1_1") (pintype "passive"))
      (node (ref "U40") (pin "3") (pinfunction "C(3)_3") (pintype "input"))
    )
    (net (code "53") (name "B_MI_STEP_WF") (class "Default")
      (node (ref "J18") (pin "6") (pinfunction "6-INPUT_B-_6") (pintype "passive"))
      (node (ref "R103") (pin "1") (pinfunction "1_1") (pintype "passive"))
      (node (ref "U52") (pin "3") (pinfunction "C(3)_3") (pintype "input"))
    )
    (net (code "54") (name "B_MI_STEP_X") (class "Default")
      (node (ref "J2") (pin "6") (pinfunction "6-INPUT_B-_6") (pintype "passive"))
      (node (ref "R8") (pin "1") (pinfunction "1_1") (pintype "passive"))
      (node (ref "U4") (pin "3") (pinfunction "C(3)_3") (pintype "input"))
    )
    (net (code "55") (name "B_MI_STEP_Y") (class "Default")
      (node (ref "J6") (pin "6") (pinfunction "6-INPUT_B-_6") (pintype "passive"))
      (node (ref "R31") (pin "1") (pinfunction "1_1") (pintype "passive"))
      (node (ref "U16") (pin "3") (pinfunction "C(3)_3") (pintype "input"))
    )
    (net (code "56") (name "B_MI_STEP_Z") (class "Default")
      (node (ref "J10") (pin "6") (pinfunction "6-INPUT_B-_6") (pintype "passive"))
      (node (ref "R55") (pin "1") (pinfunction "1_1") (pintype "passive"))
      (node (ref "U28") (pin "3") (pinfunction "C(3)_3") (pintype "input"))
    )
    (net (code "57") (name "B_STEP_A") (class "Default")
      (node (ref "J3") (pin "P$16") (pinfunction "P$16_P$16") (pintype "bidirectional"))
      (node (ref "R80") (pin "1") (pinfunction "1_1") (pintype "passive"))
    )
    (net (code "58") (name "B_STEP_X") (class "Default")
      (node (ref "J3") (pin "P$1") (pinfunction "P$1_P$1") (pintype "bidirectional"))
      (node (ref "R4") (pin "1") (pinfunction "1_1") (pintype "passive"))
    )
    (net (code "59") (name "B_STEP_Y") (class "Default")
      (node (ref "J3") (pin "P$5") (pinfunction "P$5_P$5") (pintype "bidirectional"))
      (node (ref "R32") (pin "1") (pinfunction "1_1") (pintype "passive"))
    )
    (net (code "60") (name "B_STEP_Z") (class "Default")
      (node (ref "J3") (pin "P$12") (pinfunction "P$12_P$12") (pintype "bidirectional"))
      (node (ref "R56") (pin "1") (pinfunction "1_1") (pintype "passive"))
    )
    (net (code "61") (name "ENABLE") (class "Default")
      (node (ref "J7") (pin "P$2") (pinfunction "P$2_P$2") (pintype "bidirectional"))
      (node (ref "R100") (pin "1") (pinfunction "1_1") (pintype "passive"))
      (node (ref "R106") (pin "1") (pinfunction "1_1") (pintype "passive"))
      (node (ref "R28") (pin "1") (pinfunction "1_1") (pintype "passive"))
      (node (ref "R3") (pin "1") (pinfunction "1_1") (pintype "passive"))
      (node (ref "R34") (pin "1") (pinfunction "1_1") (pintype "passive"))
      (node (ref "R52") (pin "1") (pinfunction "1_1") (pintype "passive"))
      (node (ref "R58") (pin "1") (pinfunction "1_1") (pintype "passive"))
      (node (ref "R6") (pin "1") (pinfunction "1_1") (pintype "passive"))
      (node (ref "R76") (pin "1") (pinfunction "1_1") (pintype "passive"))
      (node (ref "R82") (pin "1") (pinfunction "1_1") (pintype "passive"))
    )
    (net (code "62") (name "GND") (class "Default")
      (node (ref "J7") (pin "P$1") (pinfunction "P$1_P$1") (pintype "bidirectional"))
      (node (ref "J7") (pin "P$3") (pinfunction "P$3_P$3") (pintype "bidirectional"))
      (node (ref "U1") (pin "2") (pinfunction "E(1)_2") (pintype "output"))
      (node (ref "U13") (pin "2") (pinfunction "E(1)_2") (pintype "output"))
      (node (ref "U14") (pin "2") (pinfunction "E(1)_2") (pintype "output"))
      (node (ref "U15") (pin "2") (pinfunction "E(1)_2") (pintype "output"))
      (node (ref "U16") (pin "2") (pinfunction "E(1)_2") (pintype "output"))
      (node (ref "U17") (pin "2") (pinfunction "E(1)_2") (pintype "output"))
      (node (ref "U18") (pin "2") (pinfunction "E(1)_2") (pintype "output"))
      (node (ref "U2") (pin "2") (pinfunction "E(1)_2") (pintype "output"))
      (node (ref "U25") (pin "2") (pinfunction "E(1)_2") (pintype "output"))
      (node (ref "U26") (pin "2") (pinfunction "E(1)_2") (pintype "output"))
      (node (ref "U27") (pin "2") (pinfunction "E(1)_2") (pintype "output"))
      (node (ref "U28") (pin "2") (pinfunction "E(1)_2") (pintype "output"))
      (node (ref "U29") (pin "2") (pinfunction "E(1)_2") (pintype "output"))
      (node (ref "U3") (pin "2") (pinfunction "E(1)_2") (pintype "output"))
      (node (ref "U30") (pin "2") (pinfunction "E(1)_2") (pintype "output"))
      (node (ref "U37") (pin "2") (pinfunction "E(1)_2") (pintype "output"))
      (node (ref "U38") (pin "2") (pinfunction "E(1)_2") (pintype "output"))
      (node (ref "U39") (pin "2") (pinfunction "E(1)_2") (pintype "output"))
      (node (ref "U4") (pin "2") (pinfunction "E(1)_2") (pintype "output"))
      (node (ref "U40") (pin "2") (pinfunction "E(1)_2") (pintype "output"))
      (node (ref "U41") (pin "2") (pinfunction "E(1)_2") (pintype "output"))
      (node (ref "U42") (pin "2") (pinfunction "E(1)_2") (pintype "output"))
      (node (ref "U49") (pin "2") (pinfunction "E(1)_2") (pintype "output"))
      (node (ref "U5") (pin "2") (pinfunction "E(1)_2") (pintype "output"))
      (node (ref "U50") (pin "2") (pinfunction "E(1)_2") (pintype "output"))
      (node (ref "U51") (pin "2") (pinfunction "E(1)_2") (pintype "output"))
      (node (ref "U52") (pin "2") (pinfunction "E(1)_2") (pintype "output"))
      (node (ref "U53") (pin "2") (pinfunction "E(1)_2") (pintype "output"))
      (node (ref "U54") (pin "2") (pinfunction "E(1)_2") (pintype "output"))
      (node (ref "U6") (pin "2") (pinfunction "E(1)_2") (pintype "output"))
    )
    (net (code "63") (name "Net-(U1-B(2))") (class "Default")
      (node (ref "R1") (pin "2") (pinfunction "2_2") (pintype "passive"))
      (node (ref "U1") (pin "1") (pinfunction "B(2)_1") (pintype "input"))
    )
    (net (code "64") (name "Net-(U2-B(2))") (class "Default")
      (node (ref "R2") (pin "2") (pinfunction "2_2") (pintype "passive"))
      (node (ref "U2") (pin "1") (pinfunction "B(2)_1") (pintype "input"))
    )
    (net (code "65") (name "Net-(U3-B(2))") (class "Default")
      (node (ref "R3") (pin "2") (pinfunction "2_2") (pintype "passive"))
      (node (ref "U3") (pin "1") (pinfunction "B(2)_1") (pintype "input"))
    )
    (net (code "66") (name "Net-(U4-B(2))") (class "Default")
      (node (ref "R4") (pin "2") (pinfunction "2_2") (pintype "passive"))
      (node (ref "U4") (pin "1") (pinfunction "B(2)_1") (pintype "input"))
    )
    (net (code "67") (name "Net-(U5-B(2))") (class "Default")
      (node (ref "R5") (pin "2") (pinfunction "2_2") (pintype "passive"))
      (node (ref "U5") (pin "1") (pinfunction "B(2)_1") (pintype "input"))
    )
    (net (code "68") (name "Net-(U6-B(2))") (class "Default")
      (node (ref "R6") (pin "2") (pinfunction "2_2") (pintype "passive"))
      (node (ref "U6") (pin "1") (pinfunction "B(2)_1") (pintype "input"))
    )
    (net (code "69") (name "Net-(U13-B(2))") (class "Default")
      (node (ref "R26") (pin "2") (pinfunction "2_2") (pintype "passive"))
      (node (ref "U13") (pin "1") (pinfunction "B(2)_1") (pintype "input"))
    )
    (net (code "70") (name "Net-(U14-B(2))") (class "Default")
      (node (ref "R27") (pin "2") (pinfunction "2_2") (pintype "passive"))
      (node (ref "U14") (pin "1") (pinfunction "B(2)_1") (pintype "input"))
    )
    (net (code "71") (name "Net-(U15-B(2))") (class "Default")
      (node (ref "R28") (pin "2") (pinfunction "2_2") (pintype "passive"))
      (node (ref "U15") (pin "1") (pinfunction "B(2)_1") (pintype "input"))
    )
    (net (code "72") (name "Net-(U16-B(2))") (class "Default")
      (node (ref "R32") (pin "2") (pinfunction "2_2") (pintype "passive"))
      (node (ref "U16") (pin "1") (pinfunction "B(2)_1") (pintype "input"))
    )
    (net (code "73") (name "Net-(U17-B(2))") (class "Default")
      (node (ref "R33") (pin "2") (pinfunction "2_2") (pintype "passive"))
      (node (ref "U17") (pin "1") (pinfunction "B(2)_1") (pintype "input"))
    )
    (net (code "74") (name "Net-(U18-B(2))") (class "Default")
      (node (ref "R34") (pin "2") (pinfunction "2_2") (pintype "passive"))
      (node (ref "U18") (pin "1") (pinfunction "B(2)_1") (pintype "input"))
    )
    (net (code "75") (name "Net-(U25-B(2))") (class "Default")
      (node (ref "R50") (pin "2") (pinfunction "2_2") (pintype "passive"))
      (node (ref "U25") (pin "1") (pinfunction "B(2)_1") (pintype "input"))
    )
    (net (code "76") (name "Net-(U26-B(2))") (class "Default")
      (node (ref "R51") (pin "2") (pinfunction "2_2") (pintype "passive"))
      (node (ref "U26") (pin "1") (pinfunction "B(2)_1") (pintype "input"))
    )
    (net (code "77") (name "Net-(U27-B(2))") (class "Default")
      (node (ref "R52") (pin "2") (pinfunction "2_2") (pintype "passive"))
      (node (ref "U27") (pin "1") (pinfunction "B(2)_1") (pintype "input"))
    )
    (net (code "78") (name "Net-(U28-B(2))") (class "Default")
      (node (ref "R56") (pin "2") (pinfunction "2_2") (pintype "passive"))
      (node (ref "U28") (pin "1") (pinfunction "B(2)_1") (pintype "input"))
    )
    (net (code "79") (name "Net-(U29-B(2))") (class "Default")
      (node (ref "R57") (pin "2") (pinfunction "2_2") (pintype "passive"))
      (node (ref "U29") (pin "1") (pinfunction "B(2)_1") (pintype "input"))
    )
    (net (code "80") (name "Net-(U30-B(2))") (class "Default")
      (node (ref "R58") (pin "2") (pinfunction "2_2") (pintype "passive"))
      (node (ref "U30") (pin "1") (pinfunction "B(2)_1") (pintype "input"))
    )
    (net (code "81") (name "Net-(U37-B(2))") (class "Default")
      (node (ref "R74") (pin "2") (pinfunction "2_2") (pintype "passive"))
      (node (ref "U37") (pin "1") (pinfunction "B(2)_1") (pintype "input"))
    )
    (net (code "82") (name "Net-(U38-B(2))") (class "Default")
      (node (ref "R75") (pin "2") (pinfunction "2_2") (pintype "passive"))
      (node (ref "U38") (pin "1") (pinfunction "B(2)_1") (pintype "input"))
    )
    (net (code "83") (name "Net-(U39-B(2))") (class "Default")
      (node (ref "R76") (pin "2") (pinfunction "2_2") (pintype "passive"))
      (node (ref "U39") (pin "1") (pinfunction "B(2)_1") (pintype "input"))
    )
    (net (code "84") (name "Net-(U40-B(2))") (class "Default")
      (node (ref "R80") (pin "2") (pinfunction "2_2") (pintype "passive"))
      (node (ref "U40") (pin "1") (pinfunction "B(2)_1") (pintype "input"))
    )
    (net (code "85") (name "Net-(U41-B(2))") (class "Default")
      (node (ref "R81") (pin "2") (pinfunction "2_2") (pintype "passive"))
      (node (ref "U41") (pin "1") (pinfunction "B(2)_1") (pintype "input"))
    )
    (net (code "86") (name "Net-(U42-B(2))") (class "Default")
      (node (ref "R82") (pin "2") (pinfunction "2_2") (pintype "passive"))
      (node (ref "U42") (pin "1") (pinfunction "B(2)_1") (pintype "input"))
    )
    (net (code "87") (name "Net-(U49-B(2))") (class "Default")
      (node (ref "R98") (pin "2") (pinfunction "2_2") (pintype "passive"))
      (node (ref "U49") (pin "1") (pinfunction "B(2)_1") (pintype "input"))
    )
    (net (code "88") (name "Net-(U50-B(2))") (class "Default")
      (node (ref "R99") (pin "2") (pinfunction "2_2") (pintype "passive"))
      (node (ref "U50") (pin "1") (pinfunction "B(2)_1") (pintype "input"))
    )
    (net (code "89") (name "Net-(U51-B(2))") (class "Default")
      (node (ref "R100") (pin "2") (pinfunction "2_2") (pintype "passive"))
      (node (ref "U51") (pin "1") (pinfunction "B(2)_1") (pintype "input"))
    )
    (net (code "90") (name "Net-(U52-B(2))") (class "Default")
      (node (ref "R104") (pin "2") (pinfunction "2_2") (pintype "passive"))
      (node (ref "U52") (pin "1") (pinfunction "B(2)_1") (pintype "input"))
    )
    (net (code "91") (name "Net-(U53-B(2))") (class "Default")
      (node (ref "R105") (pin "2") (pinfunction "2_2") (pintype "passive"))
      (node (ref "U53") (pin "1") (pinfunction "B(2)_1") (pintype "input"))
    )
    (net (code "92") (name "Net-(U54-B(2))") (class "Default")
      (node (ref "R106") (pin "2") (pinfunction "2_2") (pintype "passive"))
      (node (ref "U54") (pin "1") (pinfunction "B(2)_1") (pintype "input"))
    )
    (net (code "93") (name "VDD12") (class "Default")
      (node (ref "J1") (pin "1") (pinfunction "1-HLFB+_1") (pintype "passive"))
      (node (ref "J1") (pin "2") (pinfunction "2-INPUT_B+_2") (pintype "passive"))
      (node (ref "J1") (pin "3") (pinfunction "3-INPUT_A+_3") (pintype "passive"))
      (node (ref "J1") (pin "4") (pinfunction "4-ENABLE+_4") (pintype "passive"))
      (node (ref "J10") (pin "1") (pinfunction "1-HLFB+_1") (pintype "passive"))
      (node (ref "J10") (pin "2") (pinfunction "2-INPUT_B+_2") (pintype "passive"))
      (node (ref "J10") (pin "3") (pinfunction "3-INPUT_A+_3") (pintype "passive"))
      (node (ref "J10") (pin "4") (pinfunction "4-ENABLE+_4") (pintype "passive"))
      (node (ref "J13") (pin "1") (pinfunction "1-HLFB+_1") (pintype "passive"))
      (node (ref "J13") (pin "2") (pinfunction "2-INPUT_B+_2") (pintype "passive"))
      (node (ref "J13") (pin "3") (pinfunction "3-INPUT_A+_3") (pintype "passive"))
      (node (ref "J13") (pin "4") (pinfunction "4-ENABLE+_4") (pintype "passive"))
      (node (ref "J14") (pin "1") (pinfunction "1-HLFB+_1") (pintype "passive"))
      (node (ref "J14") (pin "2") (pinfunction "2-INPUT_B+_2") (pintype "passive"))
      (node (ref "J14") (pin "3") (pinfunction "3-INPUT_A+_3") (pintype "passive"))
      (node (ref "J14") (pin "4") (pinfunction "4-ENABLE+_4") (pintype "passive"))
      (node (ref "J17") (pin "1") (pinfunction "1-HLFB+_1") (pintype "passive"))
      (node (ref "J17") (pin "2") (pinfunction "2-INPUT_B+_2") (pintype "passive"))
      (node (ref "J17") (pin "3") (pinfunction "3-INPUT_A+_3") (pintype "passive"))
      (node (ref "J17") (pin "4") (pinfunction "4-ENABLE+_4") (pintype "passive"))
      (node (ref "J18") (pin "1") (pinfunction "1-HLFB+_1") (pintype "passive"))
      (node (ref "J18") (pin "2") (pinfunction "2-INPUT_B+_2") (pintype "passive"))
      (node (ref "J18") (pin "3") (pinfunction "3-INPUT_A+_3") (pintype "passive"))
      (node (ref "J18") (pin "4") (pinfunction "4-ENABLE+_4") (pintype "passive"))
      (node (ref "J2") (pin "1") (pinfunction "1-HLFB+_1") (pintype "passive"))
      (node (ref "J2") (pin "2") (pinfunction "2-INPUT_B+_2") (pintype "passive"))
      (node (ref "J2") (pin "3") (pinfunction "3-INPUT_A+_3") (pintype "passive"))
      (node (ref "J2") (pin "4") (pinfunction "4-ENABLE+_4") (pintype "passive"))
      (node (ref "J5") (pin "1") (pinfunction "1-HLFB+_1") (pintype "passive"))
      (node (ref "J5") (pin "2") (pinfunction "2-INPUT_B+_2") (pintype "passive"))
      (node (ref "J5") (pin "3") (pinfunction "3-INPUT_A+_3") (pintype "passive"))
      (node (ref "J5") (pin "4") (pinfunction "4-ENABLE+_4") (pintype "passive"))
      (node (ref "J6") (pin "1") (pinfunction "1-HLFB+_1") (pintype "passive"))
      (node (ref "J6") (pin "2") (pinfunction "2-INPUT_B+_2") (pintype "passive"))
      (node (ref "J6") (pin "3") (pinfunction "3-INPUT_A+_3") (pintype "passive"))
      (node (ref "J6") (pin "4") (pinfunction "4-ENABLE+_4") (pintype "passive"))
      (node (ref "J7") (pin "P$4") (pinfunction "P$4_P$4") (pintype "bidirectional"))
      (node (ref "J9") (pin "1") (pinfunction "1-HLFB+_1") (pintype "passive"))
      (node (ref "J9") (pin "2") (pinfunction "2-INPUT_B+_2") (pintype "passive"))
      (node (ref "J9") (pin "3") (pinfunction "3-INPUT_A+_3") (pintype "passive"))
      (node (ref "J9") (pin "4") (pinfunction "4-ENABLE+_4") (pintype "passive"))
      (node (ref "R10") (pin "2") (pinfunction "2_2") (pintype "passive"))
      (node (ref "R101") (pin "2") (pinfunction "2_2") (pintype "passive"))
      (node (ref "R102") (pin "2") (pinfunction "2_2") (pintype "passive"))
      (node (ref "R103") (pin "2") (pinfunction "2_2") (pintype "passive"))
      (node (ref "R107") (pin "2") (pinfunction "2_2") (pintype "passive"))
      (node (ref "R108") (pin "2") (pinfunction "2_2") (pintype "passive"))
      (node (ref "R11") (pin "2") (pinfunction "2_2") (pintype "passive"))
      (node (ref "R12") (pin "2") (pinfunction "2_2") (pintype "passive"))
      (node (ref "R25") (pin "2") (pinfunction "2_2") (pintype "passive"))
      (node (ref "R29") (pin "2") (pinfunction "2_2") (pintype "passive"))
      (node (ref "R30") (pin "2") (pinfunction "2_2") (pintype "passive"))
      (node (ref "R31") (pin "2") (pinfunction "2_2") (pintype "passive"))
      (node (ref "R35") (pin "2") (pinfunction "2_2") (pintype "passive"))
      (node (ref "R36") (pin "2") (pinfunction "2_2") (pintype "passive"))
      (node (ref "R49") (pin "2") (pinfunction "2_2") (pintype "passive"))
      (node (ref "R53") (pin "2") (pinfunction "2_2") (pintype "passive"))
      (node (ref "R54") (pin "2") (pinfunction "2_2") (pintype "passive"))
      (node (ref "R55") (pin "2") (pinfunction "2_2") (pintype "passive"))
      (node (ref "R59") (pin "2") (pinfunction "2_2") (pintype "passive"))
      (node (ref "R60") (pin "2") (pinfunction "2_2") (pintype "passive"))
      (node (ref "R7") (pin "2") (pinfunction "2_2") (pintype "passive"))
      (node (ref "R73") (pin "2") (pinfunction "2_2") (pintype "passive"))
      (node (ref "R77") (pin "2") (pinfunction "2_2") (pintype "passive"))
      (node (ref "R78") (pin "2") (pinfunction "2_2") (pintype "passive"))
      (node (ref "R79") (pin "2") (pinfunction "2_2") (pintype "passive"))
      (node (ref "R8") (pin "2") (pinfunction "2_2") (pintype "passive"))
      (node (ref "R83") (pin "2") (pinfunction "2_2") (pintype "passive"))
      (node (ref "R84") (pin "2") (pinfunction "2_2") (pintype "passive"))
      (node (ref "R9") (pin "2") (pinfunction "2_2") (pintype "passive"))
      (node (ref "R97") (pin "2") (pinfunction "2_2") (pintype "passive"))
    )
  )
)
